# heart_ckt.net
KiCad netlist of a schematic drawn in EAGLE
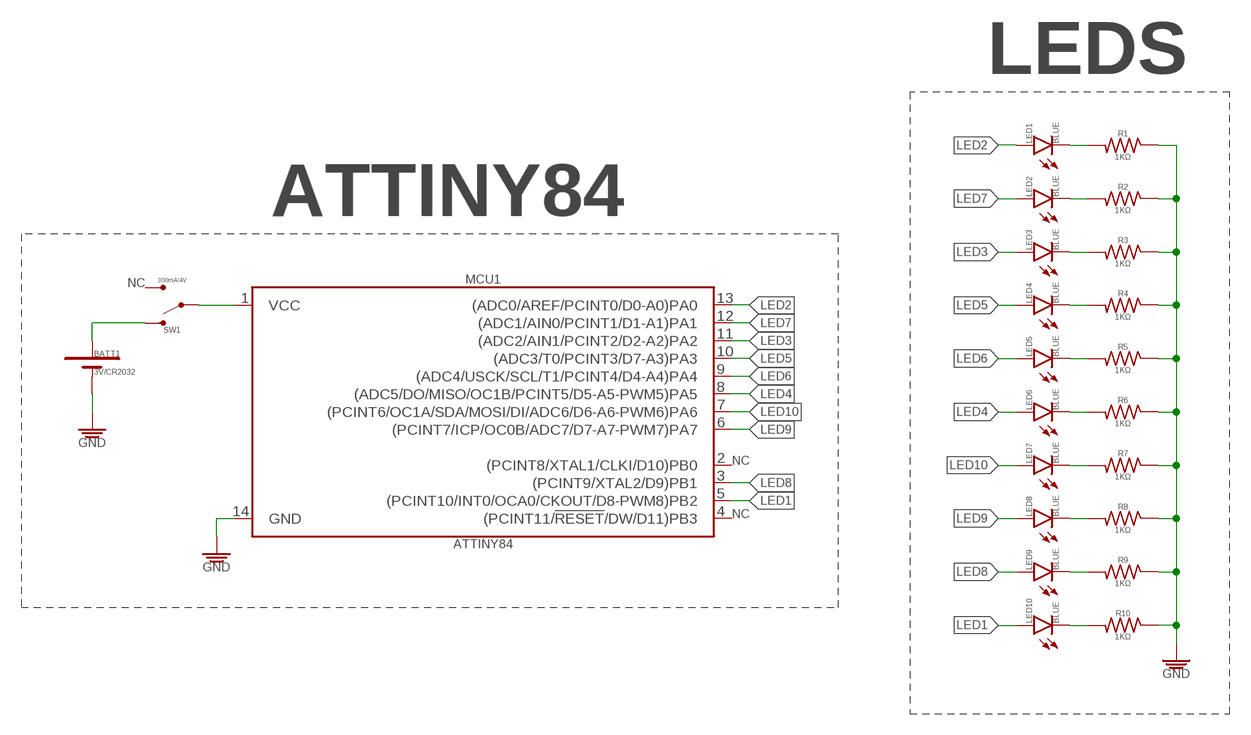
[diagram p0: schematic, sheet 1]

(export (version "E")
  (design (tool "Eeschema 10.0.6"))
  (components
    (comp (ref "BATT1")
      (value "3V/CR2032")
      (footprint "eagle-import:BATTERY_COINCELL-20MM-PTH")
      (fields
        (field (name "MFR") "Panasonic - BSG")
        (field (name "MPN") "CR2032")
        (field (name "CREATOR") "MrSwirlyEyes")
      )
      (libsource (lib "eagle-import") (part "BATTERY_CELL_COINCELL-CR2032-20MM_PTH"))
    )
    (comp (ref "LED1")
      (value "BLUE")
      (footprint "eagle-import:LED_SMD-805_")
      (fields
        (field (name "MFR") "Lite-On Inc.")
        (field (name "MPN") "LTST-C170TBKT")
        (field (name "CREATOR") "MrSwirlyEyes")
      )
      (libsource (lib "eagle-import") (part "LED_SMD-0805_DISCRETE_BLUE"))
    )
    (comp (ref "LED2")
      (value "BLUE")
      (footprint "eagle-import:LED_SMD-805_")
      (fields
        (field (name "MFR") "Lite-On Inc.")
        (field (name "MPN") "LTST-C170TBKT")
        (field (name "CREATOR") "MrSwirlyEyes")
      )
      (libsource (lib "eagle-import") (part "LED_SMD-0805_DISCRETE_BLUE"))
    )
    (comp (ref "LED3")
      (value "BLUE")
      (footprint "eagle-import:LED_SMD-805_")
      (fields
        (field (name "MFR") "Lite-On Inc.")
        (field (name "MPN") "LTST-C170TBKT")
        (field (name "CREATOR") "MrSwirlyEyes")
      )
      (libsource (lib "eagle-import") (part "LED_SMD-0805_DISCRETE_BLUE"))
    )
    (comp (ref "LED4")
      (value "BLUE")
      (footprint "eagle-import:LED_SMD-805_")
      (fields
        (field (name "MFR") "Lite-On Inc.")
        (field (name "MPN") "LTST-C170TBKT")
        (field (name "CREATOR") "MrSwirlyEyes")
      )
      (libsource (lib "eagle-import") (part "LED_SMD-0805_DISCRETE_BLUE"))
    )
    (comp (ref "LED5")
      (value "BLUE")
      (footprint "eagle-import:LED_SMD-805_")
      (fields
        (field (name "MFR") "Lite-On Inc.")
        (field (name "MPN") "LTST-C170TBKT")
        (field (name "CREATOR") "MrSwirlyEyes")
      )
      (libsource (lib "eagle-import") (part "LED_SMD-0805_DISCRETE_BLUE"))
    )
    (comp (ref "LED6")
      (value "BLUE")
      (footprint "eagle-import:LED_SMD-805_")
      (fields
        (field (name "MFR") "Lite-On Inc.")
        (field (name "MPN") "LTST-C170TBKT")
        (field (name "CREATOR") "MrSwirlyEyes")
      )
      (libsource (lib "eagle-import") (part "LED_SMD-0805_DISCRETE_BLUE"))
    )
    (comp (ref "LED7")
      (value "BLUE")
      (footprint "eagle-import:LED_SMD-805_")
      (fields
        (field (name "MFR") "Lite-On Inc.")
        (field (name "MPN") "LTST-C170TBKT")
        (field (name "CREATOR") "MrSwirlyEyes")
      )
      (libsource (lib "eagle-import") (part "LED_SMD-0805_DISCRETE_BLUE"))
    )
    (comp (ref "LED8")
      (value "BLUE")
      (footprint "eagle-import:LED_SMD-805_")
      (fields
        (field (name "MFR") "Lite-On Inc.")
        (field (name "MPN") "LTST-C170TBKT")
        (field (name "CREATOR") "MrSwirlyEyes")
      )
      (libsource (lib "eagle-import") (part "LED_SMD-0805_DISCRETE_BLUE"))
    )
    (comp (ref "LED9")
      (value "BLUE")
      (footprint "eagle-import:LED_SMD-805_")
      (fields
        (field (name "MFR") "Lite-On Inc.")
        (field (name "MPN") "LTST-C170TBKT")
        (field (name "CREATOR") "MrSwirlyEyes")
      )
      (libsource (lib "eagle-import") (part "LED_SMD-0805_DISCRETE_BLUE"))
    )
    (comp (ref "LED10")
      (value "BLUE")
      (footprint "eagle-import:LED_SMD-805_")
      (fields
        (field (name "MFR") "Lite-On Inc.")
        (field (name "MPN") "LTST-C170TBKT")
        (field (name "CREATOR") "MrSwirlyEyes")
      )
      (libsource (lib "eagle-import") (part "LED_SMD-0805_DISCRETE_BLUE"))
    )
    (comp (ref "MCU1")
      (value "ATTINY84")
      (footprint "eagle-import:SO-14")
      (fields
        (field (name "MFR") "Microchip Technology")
        (field (name "MPN") "ATTINY84A-SSU")
        (field (name "CREATOR") "MrSwirlyEyes")
      )
      (libsource (lib "eagle-import") (part "ATTINY84_SO-14"))
    )
    (comp (ref "R1")
      (value "1KΩ")
      (footprint "eagle-import:RESISTOR_SMD-805")
      (fields
        (field (name "MFR") "Yageo")
        (field (name "MPN") "RC0805JR-071KL ")
        (field (name "CREATOR") "Kenmei")
      )
      (libsource (lib "eagle-import") (part "1KΩ_SMD-0805_1/8W-5%"))
    )
    (comp (ref "R2")
      (value "1KΩ")
      (footprint "eagle-import:RESISTOR_SMD-805")
      (fields
        (field (name "MFR") "Yageo")
        (field (name "MPN") "RC0805JR-071KL ")
        (field (name "CREATOR") "Kenmei")
      )
      (libsource (lib "eagle-import") (part "1KΩ_SMD-0805_1/8W-5%"))
    )
    (comp (ref "R3")
      (value "1KΩ")
      (footprint "eagle-import:RESISTOR_SMD-805")
      (fields
        (field (name "MFR") "Yageo")
        (field (name "MPN") "RC0805JR-071KL ")
        (field (name "CREATOR") "Kenmei")
      )
      (libsource (lib "eagle-import") (part "1KΩ_SMD-0805_1/8W-5%"))
    )
    (comp (ref "R4")
      (value "1KΩ")
      (footprint "eagle-import:RESISTOR_SMD-805")
      (fields
        (field (name "MFR") "Yageo")
        (field (name "MPN") "RC0805JR-071KL ")
        (field (name "CREATOR") "Kenmei")
      )
      (libsource (lib "eagle-import") (part "1KΩ_SMD-0805_1/8W-5%"))
    )
    (comp (ref "R5")
      (value "1KΩ")
      (footprint "eagle-import:RESISTOR_SMD-805")
      (fields
        (field (name "MFR") "Yageo")
        (field (name "MPN") "RC0805JR-071KL ")
        (field (name "CREATOR") "Kenmei")
      )
      (libsource (lib "eagle-import") (part "1KΩ_SMD-0805_1/8W-5%"))
    )
    (comp (ref "R6")
      (value "1KΩ")
      (footprint "eagle-import:RESISTOR_SMD-805")
      (fields
        (field (name "MFR") "Yageo")
        (field (name "MPN") "RC0805JR-071KL ")
        (field (name "CREATOR") "Kenmei")
      )
      (libsource (lib "eagle-import") (part "1KΩ_SMD-0805_1/8W-5%"))
    )
    (comp (ref "R7")
      (value "1KΩ")
      (footprint "eagle-import:RESISTOR_SMD-805")
      (fields
        (field (name "MFR") "Yageo")
        (field (name "MPN") "RC0805JR-071KL ")
        (field (name "CREATOR") "Kenmei")
      )
      (libsource (lib "eagle-import") (part "1KΩ_SMD-0805_1/8W-5%"))
    )
    (comp (ref "R8")
      (value "1KΩ")
      (footprint "eagle-import:RESISTOR_SMD-805")
      (fields
        (field (name "MFR") "Yageo")
        (field (name "MPN") "RC0805JR-071KL ")
        (field (name "CREATOR") "Kenmei")
      )
      (libsource (lib "eagle-import") (part "1KΩ_SMD-0805_1/8W-5%"))
    )
    (comp (ref "R9")
      (value "1KΩ")
      (footprint "eagle-import:RESISTOR_SMD-805")
      (fields
        (field (name "MFR") "Yageo")
        (field (name "MPN") "RC0805JR-071KL ")
        (field (name "CREATOR") "Kenmei")
      )
      (libsource (lib "eagle-import") (part "1KΩ_SMD-0805_1/8W-5%"))
    )
    (comp (ref "R10")
      (value "1KΩ")
      (footprint "eagle-import:RESISTOR_SMD-805")
      (fields
        (field (name "MFR") "Yageo")
        (field (name "MPN") "RC0805JR-071KL ")
        (field (name "CREATOR") "Kenmei")
      )
      (libsource (lib "eagle-import") (part "1KΩ_SMD-0805_1/8W-5%"))
    )
    (comp (ref "SW1")
      (value "300mA/4V")
      (footprint "eagle-import:SW_SLIDE_SPDT_RA_SMD_4V_300MA_6.7L-2.6W")
      (fields
        (field (name "MFR") "APEM Inc.")
        (field (name "MPN") "MA12RTR")
        (field (name "CREATOR") "MrSwirlyEyes")
      )
      (libsource (lib "eagle-import") (part "SWITCH_SPDT_RA_SMD_300MA-4V_6.7L-2.6W"))
    )
  )
  (nets
    (net (code "1") (name "GND") (class "Default")
      (node (ref "BATT1") (pin "-") (pinfunction "-_-") (pintype "power_in"))
      (node (ref "MCU1") (pin "14") (pinfunction "GND_14") (pintype "passive"))
      (node (ref "R1") (pin "1") (pinfunction "1_1") (pintype "passive"))
      (node (ref "R10") (pin "1") (pinfunction "1_1") (pintype "passive"))
      (node (ref "R2") (pin "1") (pinfunction "1_1") (pintype "passive"))
      (node (ref "R3") (pin "1") (pinfunction "1_1") (pintype "passive"))
      (node (ref "R4") (pin "1") (pinfunction "1_1") (pintype "passive"))
      (node (ref "R5") (pin "1") (pinfunction "1_1") (pintype "passive"))
      (node (ref "R6") (pin "1") (pinfunction "1_1") (pintype "passive"))
      (node (ref "R7") (pin "1") (pinfunction "1_1") (pintype "passive"))
      (node (ref "R8") (pin "1") (pinfunction "1_1") (pintype "passive"))
      (node (ref "R9") (pin "1") (pinfunction "1_1") (pintype "passive"))
    )
    (net (code "2") (name "LED1") (class "Default")
      (node (ref "LED10") (pin "A") (pinfunction "A_A") (pintype "passive"))
      (node (ref "MCU1") (pin "5") (pinfunction "(PCINT10/INT0/OCA0/CKOUT/D8-PWM8)PB2_5") (pintype "bidirectional"))
    )
    (net (code "3") (name "LED2") (class "Default")
      (node (ref "LED1") (pin "A") (pinfunction "A_A") (pintype "passive"))
      (node (ref "MCU1") (pin "13") (pinfunction "(ADC0/AREF/PCINT0/D0-A0)PA0_13") (pintype "bidirectional"))
    )
    (net (code "4") (name "LED3") (class "Default")
      (node (ref "LED3") (pin "A") (pinfunction "A_A") (pintype "passive"))
      (node (ref "MCU1") (pin "11") (pinfunction "(ADC2/AIN1/PCINT2/D2-A2)PA2_11") (pintype "bidirectional"))
    )
    (net (code "5") (name "LED4") (class "Default")
      (node (ref "LED6") (pin "A") (pinfunction "A_A") (pintype "passive"))
      (node (ref "MCU1") (pin "8") (pinfunction "(ADC5/DO/MISO/OC1B/PCINT5/D5-A5-PWM5)PA5_8") (pintype "bidirectional"))
    )
    (net (code "6") (name "LED5") (class "Default")
      (node (ref "LED4") (pin "A") (pinfunction "A_A") (pintype "passive"))
      (node (ref "MCU1") (pin "10") (pinfunction "(ADC3/T0/PCINT3/D7-A3)PA3_10") (pintype "bidirectional"))
    )
    (net (code "7") (name "LED6") (class "Default")
      (node (ref "LED5") (pin "A") (pinfunction "A_A") (pintype "passive"))
      (node (ref "MCU1") (pin "9") (pinfunction "(ADC4/USCK/SCL/T1/PCINT4/D4-A4)PA4_9") (pintype "bidirectional"))
    )
    (net (code "8") (name "LED7") (class "Default")
      (node (ref "LED2") (pin "A") (pinfunction "A_A") (pintype "passive"))
      (node (ref "MCU1") (pin "12") (pinfunction "(ADC1/AIN0/PCINT1/D1-A1)PA1_12") (pintype "bidirectional"))
    )
    (net (code "9") (name "LED8") (class "Default")
      (node (ref "LED9") (pin "A") (pinfunction "A_A") (pintype "passive"))
      (node (ref "MCU1") (pin "3") (pinfunction "(PCINT9/XTAL2/D9)PB1_3") (pintype "bidirectional"))
    )
    (net (code "10") (name "LED9") (class "Default")
      (node (ref "LED8") (pin "A") (pinfunction "A_A") (pintype "passive"))
      (node (ref "MCU1") (pin "6") (pinfunction "(PCINT7/ICP/OC0B/ADC7/D7-A7-PWM7)PA7_6") (pintype "bidirectional"))
    )
    (net (code "11") (name "LED10") (class "Default")
      (node (ref "LED7") (pin "A") (pinfunction "A_A") (pintype "passive"))
      (node (ref "MCU1") (pin "7") (pinfunction "(PCINT6/OC1A/SDA/MOSI/DI/ADC6/D6-A6-PWM6)PA6_7") (pintype "bidirectional"))
    )
    (net (code "12") (name "Net-(BATT1-Pad+)") (class "Default")
      (node (ref "BATT1") (pin "+") (pinfunction "+_+") (pintype "power_in"))
      (node (ref "SW1") (pin "1") (pinfunction "1_1") (pintype "passive"))
    )
    (net (code "13") (name "Net-(LED1-PadK)") (class "Default")
      (node (ref "LED1") (pin "K") (pinfunction "K_K") (pintype "passive"))
      (node (ref "R1") (pin "2") (pinfunction "2_2") (pintype "passive"))
    )
    (net (code "14") (name "Net-(LED2-PadK)") (class "Default")
      (node (ref "LED2") (pin "K") (pinfunction "K_K") (pintype "passive"))
      (node (ref "R2") (pin "2") (pinfunction "2_2") (pintype "passive"))
    )
    (net (code "15") (name "Net-(LED3-PadK)") (class "Default")
      (node (ref "LED3") (pin "K") (pinfunction "K_K") (pintype "passive"))
      (node (ref "R3") (pin "2") (pinfunction "2_2") (pintype "passive"))
    )
    (net (code "16") (name "Net-(LED4-PadK)") (class "Default")
      (node (ref "LED4") (pin "K") (pinfunction "K_K") (pintype "passive"))
      (node (ref "R4") (pin "2") (pinfunction "2_2") (pintype "passive"))
    )
    (net (code "17") (name "Net-(LED5-PadK)") (class "Default")
      (node (ref "LED5") (pin "K") (pinfunction "K_K") (pintype "passive"))
      (node (ref "R5") (pin "2") (pinfunction "2_2") (pintype "passive"))
    )
    (net (code "18") (name "Net-(LED6-PadK)") (class "Default")
      (node (ref "LED6") (pin "K") (pinfunction "K_K") (pintype "passive"))
      (node (ref "R6") (pin "2") (pinfunction "2_2") (pintype "passive"))
    )
    (net (code "19") (name "Net-(LED7-PadK)") (class "Default")
      (node (ref "LED7") (pin "K") (pinfunction "K_K") (pintype "passive"))
      (node (ref "R7") (pin "2") (pinfunction "2_2") (pintype "passive"))
    )
    (net (code "20") (name "Net-(LED8-PadK)") (class "Default")
      (node (ref "LED8") (pin "K") (pinfunction "K_K") (pintype "passive"))
      (node (ref "R8") (pin "2") (pinfunction "2_2") (pintype "passive"))
    )
    (net (code "21") (name "Net-(LED9-PadK)") (class "Default")
      (node (ref "LED9") (pin "K") (pinfunction "K_K") (pintype "passive"))
      (node (ref "R9") (pin "2") (pinfunction "2_2") (pintype "passive"))
    )
    (net (code "22") (name "Net-(LED10-PadK)") (class "Default")
      (node (ref "LED10") (pin "K") (pinfunction "K_K") (pintype "passive"))
      (node (ref "R10") (pin "2") (pinfunction "2_2") (pintype "passive"))
    )
    (net (code "23") (name "Net-(MCU1-VCC)") (class "Default")
      (node (ref "MCU1") (pin "1") (pinfunction "VCC_1") (pintype "passive"))
      (node (ref "SW1") (pin "2") (pinfunction "2_2") (pintype "passive"))
    )
    (net (code "24") (name "unconnected-(MCU1-(PCINT8{slash}XTAL1{slash}CLKI{slash}D10)PB0-Pad2)") (class "Default")
      (node (ref "MCU1") (pin "2") (pinfunction "(PCINT8/XTAL1/CLKI/D10)PB0_2") (pintype "bidirectional"))
    )
    (net (code "25") (name "unconnected-(MCU1-(PCINT11{slash}~{RESET}{slash}DW{slash}D11)PB3-Pad4)") (class "Default")
      (node (ref "MCU1") (pin "4") (pinfunction "(PCINT11/~{RESET}/DW/D11)PB3_4") (pintype "bidirectional"))
    )
    (net (code "26") (name "unconnected-(SW1-Pad3)") (class "Default")
      (node (ref "SW1") (pin "3") (pinfunction "3_3") (pintype "passive"))
    )
  )
)
